# A3010_Adelaide_8MB_IDE.net
KiCad netlist of a schematic drawn in Altium Designer
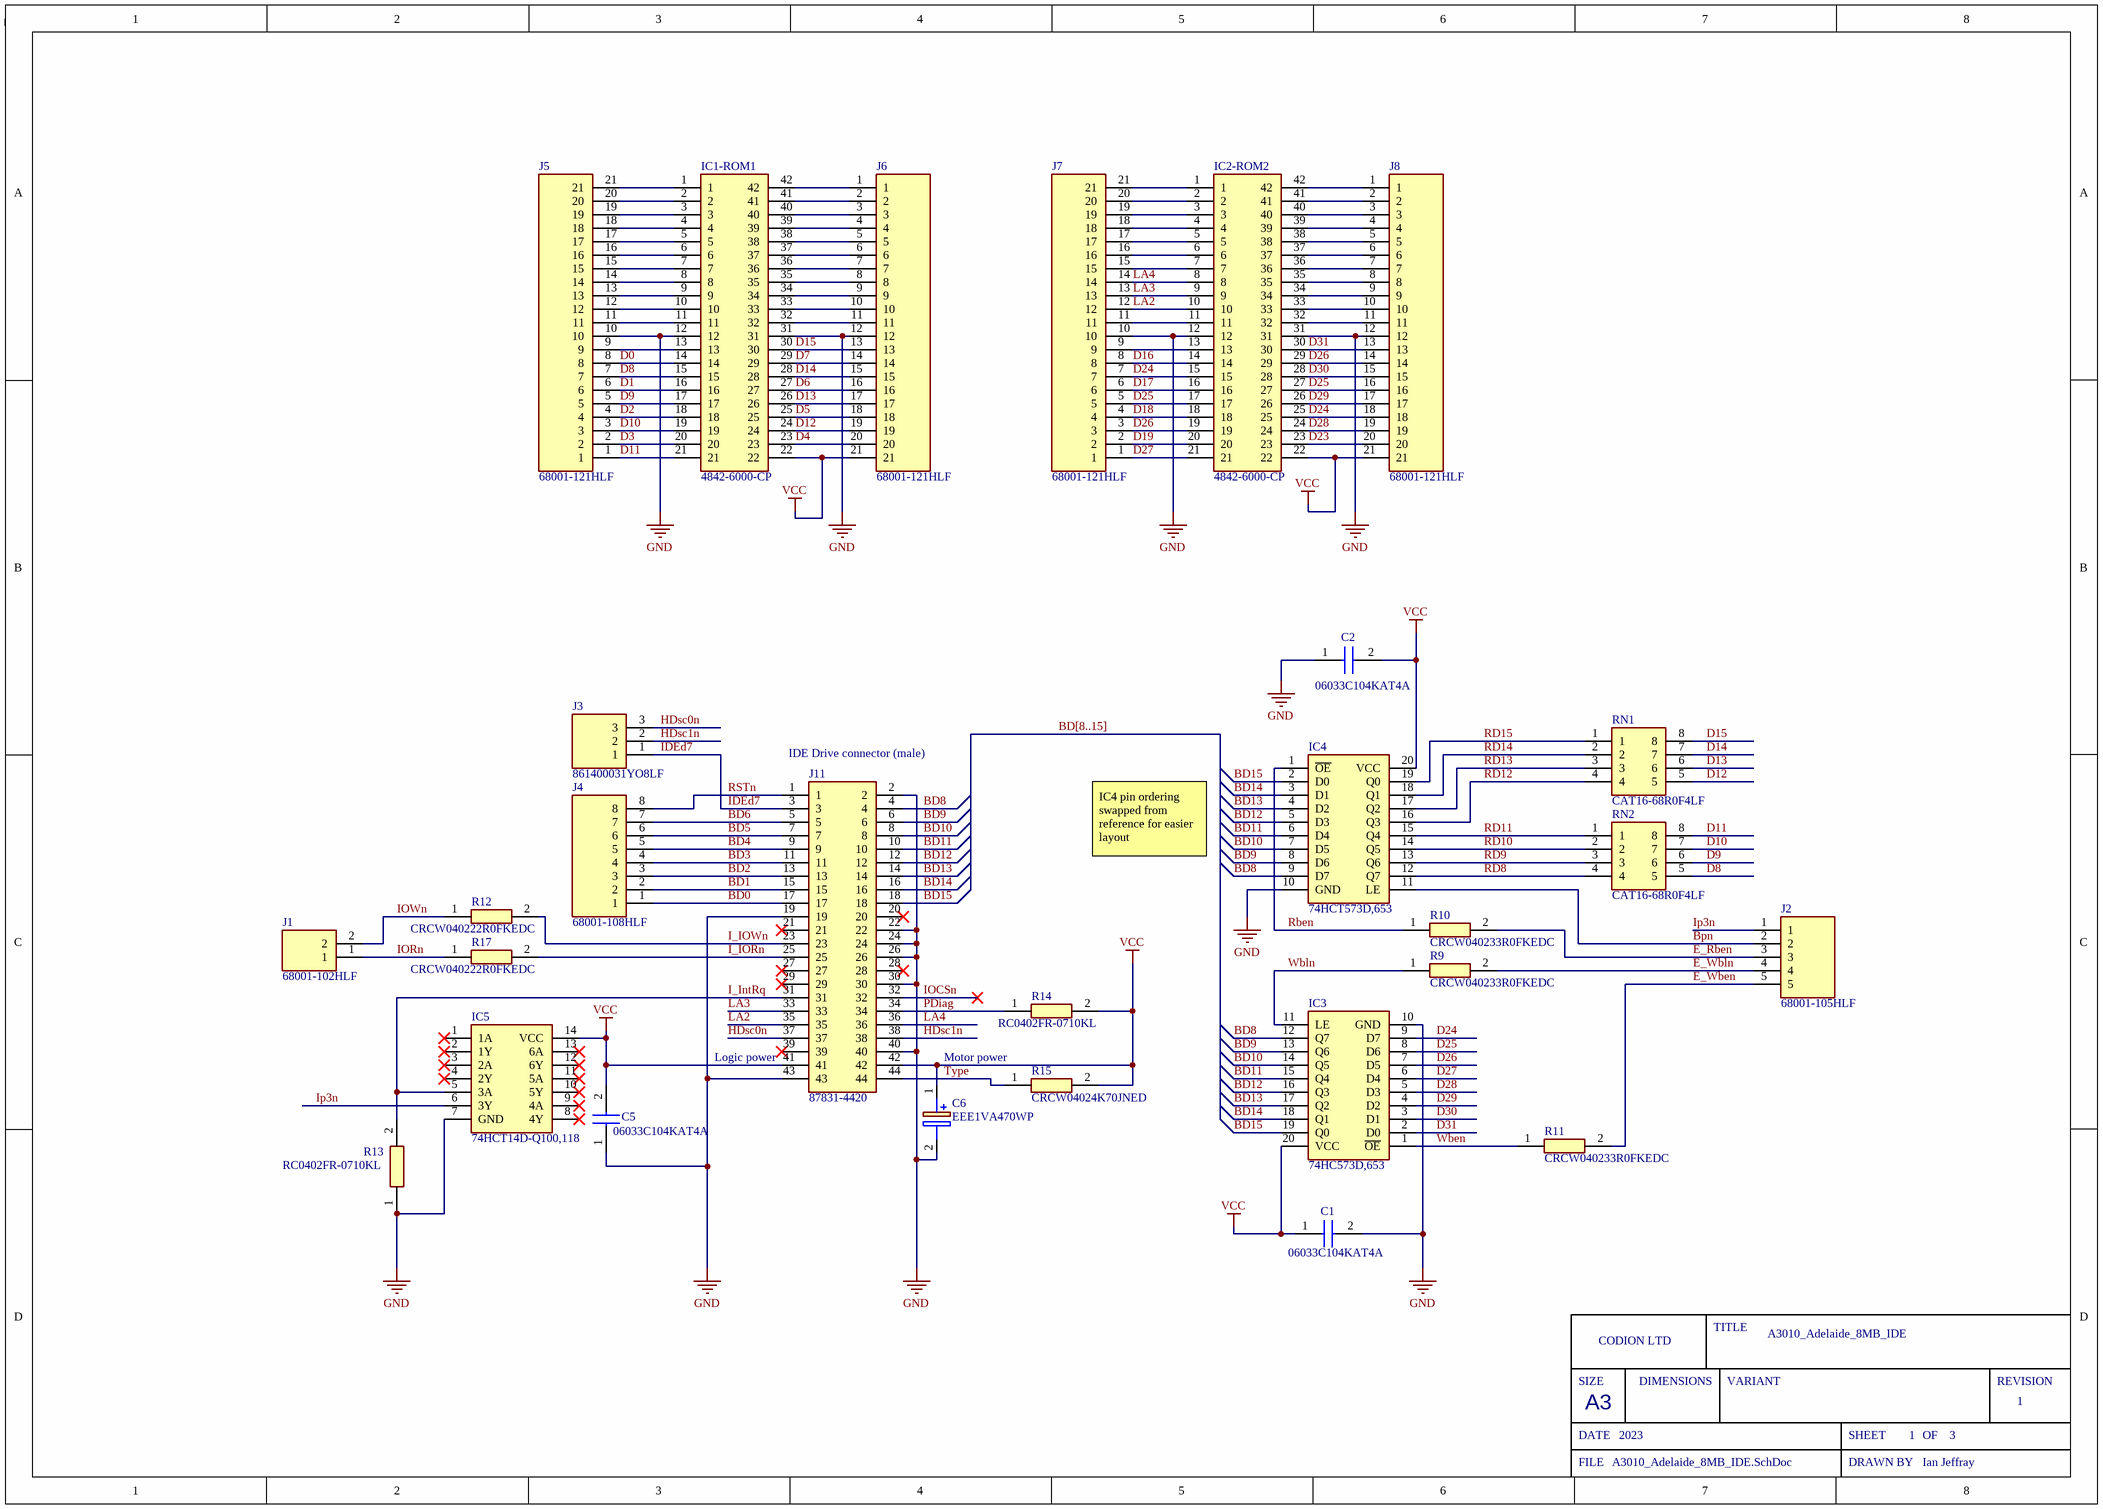
[diagram p0: A3010_Adelaide_8MB_IDE.SchDoc]

(export (version "E")
  (design (tool "Eeschema 10.0.6"))
  (components
    (comp (ref "C1")
      (value "06033C104KAT4A")
      (footprint "SamacSys:CAPC1608X90N")
      (description "Capacitor")
      (fields (field (name "MOUSER PART NUMBER") "581-06033C104KAT4A"))
      (libsource (lib "*") (part "06033C104KAT4A"))
    )
    (comp (ref "C2")
      (value "06033C104KAT4A")
      (footprint "SamacSys:CAPC1608X90N")
      (description "Capacitor")
      (fields (field (name "MOUSER PART NUMBER") "581-06033C104KAT4A"))
      (libsource (lib "*") (part "06033C104KAT4A"))
    )
    (comp (ref "C5")
      (value "06033C104KAT4A")
      (footprint "SamacSys:CAPC1608X90N")
      (description "Capacitor")
      (fields (field (name "MOUSER PART NUMBER") "581-06033C104KAT4A"))
      (libsource (lib "*") (part "06033C104KAT4A"))
    )
    (comp (ref "C6")
      (value "EEE1VA470WP")
      (footprint "SamacSys:EEE1AA101SP")
      (description "Capacitor Polarised")
      (libsource (lib "*") (part "EEE1VA470WP"))
    )
    (comp (ref "IC1-ROM1")
      (value "4842-6000-CP")
      (footprint "SamacSys:48426000CP")
      (description "Connector")
      (fields (field (name "MOUSER PART NUMBER") "517-4842-6000-CP"))
      (libsource (lib "*") (part "4842-6000-CP"))
    )
    (comp (ref "IC2-ROM2")
      (value "4842-6000-CP")
      (footprint "SamacSys:48426000CP")
      (description "Connector")
      (fields (field (name "MOUSER PART NUMBER") "517-4842-6000-CP"))
      (libsource (lib "*") (part "4842-6000-CP"))
    )
    (comp (ref "IC3")
      (value "74HC573D,653")
      (footprint "SamacSys:SOIC127P1032X265-20N")
      (description "Integrated Circuit")
      (fields (field (name "MOUSER PART NUMBER") "771-74HC573D-T"))
      (libsource (lib "*") (part "74HC573D,653"))
    )
    (comp (ref "IC4")
      (value "74HCT573D,653")
      (footprint "SamacSys:SOIC127P1032X265-20N")
      (description "Integrated Circuit")
      (fields (field (name "MOUSER PART NUMBER") "771-HCT573D653"))
      (libsource (lib "*") (part "74HCT573D,653"))
    )
    (comp (ref "IC5")
      (value "74HCT14D-Q100,118")
      (footprint "SamacSys:SOIC127P600X175-14N")
      (description "Integrated Circuit")
      (fields (field (name "MOUSER PART NUMBER") "771-74HCT14D-Q100118"))
      (libsource (lib "*") (part "74HCT14D-Q100,118"))
    )
    (comp (ref "J1")
      (value "68001-102HLF")
      (footprint "SamacSys:HDRV2W67P0X254_1X2_508X241X858P")
      (description "Connector")
      (fields (field (name "MOUSER PART NUMBER") "649-68001-102HLF"))
      (libsource (lib "*") (part "68001-102HLF"))
    )
    (comp (ref "J2")
      (value "68001-105HLF")
      (footprint "SamacSys:HDRV5W90P0X254_1X5_1270X241X1143P")
      (description "Connector")
      (fields (field (name "MOUSER PART NUMBER") "649-68001-105HLF"))
      (libsource (lib "*") (part "68001-105HLF"))
    )
    (comp (ref "J3")
      (value "861400031YO8LF")
      (footprint "SamacSys:HDRV3W63P0X254_1X3_762X254X980P")
      (description "Connector")
      (fields (field (name "MOUSER PART NUMBER") "649-861400031YO8LF"))
      (libsource (lib "*") (part "861400031YO8LF"))
    )
    (comp (ref "J4")
      (value "68001-108HLF")
      (footprint "SamacSys:HDRV8W90P0X254_1X8_2032X241X1143P")
      (description "Connector")
      (fields (field (name "MOUSER PART NUMBER") "649-68001-108HLF"))
      (libsource (lib "*") (part "68001-108HLF"))
    )
    (comp (ref "J5")
      (value "68001-121HLF")
      (footprint "SamacSys:HDRV21W67P0X254_1X21_5334X241X858P")
      (description "Connector")
      (fields (field (name "MOUSER PART NUMBER") "649-68001-121HLF"))
      (libsource (lib "") (part "68001-121HLF_1"))
    )
    (comp (ref "J6")
      (value "68001-121HLF")
      (footprint "SamacSys:HDRV21W67P0X254_1X21_5334X241X858P")
      (description "Connector")
      (fields (field (name "MOUSER PART NUMBER") "649-68001-121HLF"))
      (libsource (lib "*") (part "68001-121HLF"))
    )
    (comp (ref "J7")
      (value "68001-121HLF")
      (footprint "SamacSys:HDRV21W67P0X254_1X21_5334X241X858P")
      (description "Connector")
      (fields (field (name "MOUSER PART NUMBER") "649-68001-121HLF"))
      (libsource (lib "") (part "68001-121HLF_1"))
    )
    (comp (ref "J8")
      (value "68001-121HLF")
      (footprint "SamacSys:HDRV21W67P0X254_1X21_5334X241X858P")
      (description "Connector")
      (fields (field (name "MOUSER PART NUMBER") "649-68001-121HLF"))
      (libsource (lib "*") (part "68001-121HLF"))
    )
    (comp (ref "J11")
      (value "87831-4420")
      (footprint "SamacSys:SHDR44W55P200_2X22_4665X630X640P")
      (description "Connector")
      (fields (field (name "MOUSER PART NUMBER") "538-87831-4420"))
      (libsource (lib "*") (part "87831-4420"))
    )
    (comp (ref "R9")
      (value "CRCW040233R0FKEDC")
      (footprint "SamacSys:RESC1005X35N")
      (description "Resistor")
      (fields (field (name "MOUSER PART NUMBER") "71-CRCW040233R0FKEDC"))
      (libsource (lib "*") (part "CRCW040233R0FKEDC"))
    )
    (comp (ref "R10")
      (value "CRCW040233R0FKEDC")
      (footprint "SamacSys:RESC1005X35N")
      (description "Resistor")
      (fields (field (name "MOUSER PART NUMBER") "71-CRCW040233R0FKEDC"))
      (libsource (lib "*") (part "CRCW040233R0FKEDC"))
    )
    (comp (ref "R11")
      (value "CRCW040233R0FKEDC")
      (footprint "SamacSys:RESC1005X35N")
      (description "Resistor")
      (fields (field (name "MOUSER PART NUMBER") "71-CRCW040233R0FKEDC"))
      (libsource (lib "*") (part "CRCW040233R0FKEDC"))
    )
    (comp (ref "R12")
      (value "CRCW040222R0FKEDC")
      (footprint "SamacSys:RESC1005X35N")
      (description "Resistor")
      (fields (field (name "MOUSER PART NUMBER") "71-CRCW040222R0FKEDC"))
      (libsource (lib "*") (part "CRCW040222R0FKEDC"))
    )
    (comp (ref "R13")
      (value "RC0402FR-0710KL")
      (footprint "SamacSys:RESC1005X40N")
      (description "Resistor")
      (fields (field (name "MOUSER PART NUMBER") "603-RC0402FR-0710KL"))
      (libsource (lib "*") (part "RC0402FR-0710KL"))
    )
    (comp (ref "R14")
      (value "RC0402FR-0710KL")
      (footprint "SamacSys:RESC1005X40N")
      (description "Resistor")
      (fields (field (name "MOUSER PART NUMBER") "603-RC0402FR-0710KL"))
      (libsource (lib "") (part "RC0402FR-0710KL_1"))
    )
    (comp (ref "R15")
      (value "CRCW04024K70JNED")
      (footprint "SamacSys:RESC1005X40N")
      (description "Resistor")
      (fields (field (name "MOUSER PART NUMBER") "71-CRCW0402J-4.7K-E3"))
      (libsource (lib "*") (part "CRCW04024K70JNED"))
    )
    (comp (ref "R17")
      (value "CRCW040222R0FKEDC")
      (footprint "SamacSys:RESC1005X35N")
      (description "Resistor")
      (fields (field (name "MOUSER PART NUMBER") "71-CRCW040222R0FKEDC"))
      (libsource (lib "*") (part "CRCW040222R0FKEDC"))
    )
    (comp (ref "RN1")
      (value "CAT16-68R0F4LF")
      (footprint "SamacSys:CAT1668R0F4LF")
      (description "Resistor Network")
      (fields (field (name "MOUSER PART NUMBER") "652-CAT16-68R0F4LF"))
      (libsource (lib "*") (part "CAT16-68R0F4LF"))
    )
    (comp (ref "RN2")
      (value "CAT16-68R0F4LF")
      (footprint "SamacSys:CAT1668R0F4LF")
      (description "Resistor Network")
      (fields (field (name "MOUSER PART NUMBER") "652-CAT16-68R0F4LF"))
      (libsource (lib "*") (part "CAT16-68R0F4LF"))
    )
  )
  (nets
    (net (code "1") (name "/BD0") (class "Default")
      (node (ref "J11") (pin "17") (pinfunction "17_17") (pintype "passive"))
      (node (ref "J4") (pin "1") (pinfunction "1_1") (pintype "passive"))
    )
    (net (code "2") (name "/BD1") (class "Default")
      (node (ref "J11") (pin "15") (pinfunction "15_15") (pintype "passive"))
      (node (ref "J4") (pin "2") (pinfunction "2_2") (pintype "passive"))
    )
    (net (code "3") (name "/BD2") (class "Default")
      (node (ref "J11") (pin "13") (pinfunction "13_13") (pintype "passive"))
      (node (ref "J4") (pin "3") (pinfunction "3_3") (pintype "passive"))
    )
    (net (code "4") (name "/BD3") (class "Default")
      (node (ref "J11") (pin "11") (pinfunction "11_11") (pintype "passive"))
      (node (ref "J4") (pin "4") (pinfunction "4_4") (pintype "passive"))
    )
    (net (code "5") (name "/BD4") (class "Default")
      (node (ref "J11") (pin "9") (pinfunction "9_9") (pintype "passive"))
      (node (ref "J4") (pin "5") (pinfunction "5_5") (pintype "passive"))
    )
    (net (code "6") (name "/BD5") (class "Default")
      (node (ref "J11") (pin "7") (pinfunction "7_7") (pintype "passive"))
      (node (ref "J4") (pin "6") (pinfunction "6_6") (pintype "passive"))
    )
    (net (code "7") (name "/BD6") (class "Default")
      (node (ref "J11") (pin "5") (pinfunction "5_5") (pintype "passive"))
      (node (ref "J4") (pin "7") (pinfunction "7_7") (pintype "passive"))
    )
    (net (code "8") (name "/BD8") (class "Default")
      (node (ref "IC3") (pin "12") (pinfunction "Q7_12") (pintype "passive"))
      (node (ref "IC4") (pin "9") (pinfunction "D7_9") (pintype "passive"))
      (node (ref "J11") (pin "4") (pinfunction "4_4") (pintype "passive"))
    )
    (net (code "9") (name "/BD9") (class "Default")
      (node (ref "IC3") (pin "13") (pinfunction "Q6_13") (pintype "passive"))
      (node (ref "IC4") (pin "8") (pinfunction "D6_8") (pintype "passive"))
      (node (ref "J11") (pin "6") (pinfunction "6_6") (pintype "passive"))
    )
    (net (code "10") (name "/BD10") (class "Default")
      (node (ref "IC3") (pin "14") (pinfunction "Q5_14") (pintype "passive"))
      (node (ref "IC4") (pin "7") (pinfunction "D5_7") (pintype "passive"))
      (node (ref "J11") (pin "8") (pinfunction "8_8") (pintype "passive"))
    )
    (net (code "11") (name "/BD11") (class "Default")
      (node (ref "IC3") (pin "15") (pinfunction "Q4_15") (pintype "passive"))
      (node (ref "IC4") (pin "6") (pinfunction "D4_6") (pintype "passive"))
      (node (ref "J11") (pin "10") (pinfunction "10_10") (pintype "passive"))
    )
    (net (code "12") (name "/BD12") (class "Default")
      (node (ref "IC3") (pin "16") (pinfunction "Q3_16") (pintype "passive"))
      (node (ref "IC4") (pin "5") (pinfunction "D3_5") (pintype "passive"))
      (node (ref "J11") (pin "12") (pinfunction "12_12") (pintype "passive"))
    )
    (net (code "13") (name "/BD13") (class "Default")
      (node (ref "IC3") (pin "17") (pinfunction "Q2_17") (pintype "passive"))
      (node (ref "IC4") (pin "4") (pinfunction "D2_4") (pintype "passive"))
      (node (ref "J11") (pin "14") (pinfunction "14_14") (pintype "passive"))
    )
    (net (code "14") (name "/BD14") (class "Default")
      (node (ref "IC3") (pin "18") (pinfunction "Q1_18") (pintype "passive"))
      (node (ref "IC4") (pin "3") (pinfunction "D1_3") (pintype "passive"))
      (node (ref "J11") (pin "16") (pinfunction "16_16") (pintype "passive"))
    )
    (net (code "15") (name "/BD15") (class "Default")
      (node (ref "IC3") (pin "19") (pinfunction "Q0_19") (pintype "passive"))
      (node (ref "IC4") (pin "2") (pinfunction "D0_2") (pintype "passive"))
      (node (ref "J11") (pin "18") (pinfunction "18_18") (pintype "passive"))
    )
    (net (code "17") (name "/Bpn") (class "Default")
      (node (ref "IC4") (pin "11") (pinfunction "LE_11") (pintype "passive"))
      (node (ref "J2") (pin "2") (pinfunction "2_2") (pintype "passive"))
    )
    (net (code "18") (name "/D0") (class "Default")
      (node (ref "IC1-ROM1") (pin "14") (pinfunction "14_14") (pintype "passive"))
      (node (ref "J5") (pin "8") (pinfunction "8_8") (pintype "passive"))
    )
    (net (code "19") (name "/D1") (class "Default")
      (node (ref "IC1-ROM1") (pin "16") (pinfunction "16_16") (pintype "passive"))
      (node (ref "J5") (pin "6") (pinfunction "6_6") (pintype "passive"))
    )
    (net (code "20") (name "/D2") (class "Default")
      (node (ref "IC1-ROM1") (pin "18") (pinfunction "18_18") (pintype "passive"))
      (node (ref "J5") (pin "4") (pinfunction "4_4") (pintype "passive"))
    )
    (net (code "21") (name "/D3") (class "Default")
      (node (ref "IC1-ROM1") (pin "20") (pinfunction "20_20") (pintype "passive"))
      (node (ref "J5") (pin "2") (pinfunction "2_2") (pintype "passive"))
    )
    (net (code "22") (name "/D4") (class "Default")
      (node (ref "IC1-ROM1") (pin "23") (pinfunction "23_23") (pintype "passive"))
      (node (ref "J6") (pin "20") (pinfunction "20_20") (pintype "passive"))
    )
    (net (code "23") (name "/D5") (class "Default")
      (node (ref "IC1-ROM1") (pin "25") (pinfunction "25_25") (pintype "passive"))
      (node (ref "J6") (pin "18") (pinfunction "18_18") (pintype "passive"))
    )
    (net (code "24") (name "/D6") (class "Default")
      (node (ref "IC1-ROM1") (pin "27") (pinfunction "27_27") (pintype "passive"))
      (node (ref "J6") (pin "16") (pinfunction "16_16") (pintype "passive"))
    )
    (net (code "25") (name "/D7") (class "Default")
      (node (ref "IC1-ROM1") (pin "29") (pinfunction "29_29") (pintype "passive"))
      (node (ref "J6") (pin "14") (pinfunction "14_14") (pintype "passive"))
    )
    (net (code "26") (name "/D8") (class "Default")
      (node (ref "IC1-ROM1") (pin "15") (pinfunction "15_15") (pintype "passive"))
      (node (ref "J5") (pin "7") (pinfunction "7_7") (pintype "passive"))
      (node (ref "RN2") (pin "5") (pinfunction "5_5") (pintype "passive"))
    )
    (net (code "27") (name "/D9") (class "Default")
      (node (ref "IC1-ROM1") (pin "17") (pinfunction "17_17") (pintype "passive"))
      (node (ref "J5") (pin "5") (pinfunction "5_5") (pintype "passive"))
      (node (ref "RN2") (pin "6") (pinfunction "6_6") (pintype "passive"))
    )
    (net (code "28") (name "/D10") (class "Default")
      (node (ref "IC1-ROM1") (pin "19") (pinfunction "19_19") (pintype "passive"))
      (node (ref "J5") (pin "3") (pinfunction "3_3") (pintype "passive"))
      (node (ref "RN2") (pin "7") (pinfunction "7_7") (pintype "passive"))
    )
    (net (code "29") (name "/D11") (class "Default")
      (node (ref "IC1-ROM1") (pin "21") (pinfunction "21_21") (pintype "passive"))
      (node (ref "J5") (pin "1") (pinfunction "1_1") (pintype "passive"))
      (node (ref "RN2") (pin "8") (pinfunction "8_8") (pintype "passive"))
    )
    (net (code "30") (name "/D12") (class "Default")
      (node (ref "IC1-ROM1") (pin "24") (pinfunction "24_24") (pintype "passive"))
      (node (ref "J6") (pin "19") (pinfunction "19_19") (pintype "passive"))
      (node (ref "RN1") (pin "5") (pinfunction "5_5") (pintype "passive"))
    )
    (net (code "31") (name "/D13") (class "Default")
      (node (ref "IC1-ROM1") (pin "26") (pinfunction "26_26") (pintype "passive"))
      (node (ref "J6") (pin "17") (pinfunction "17_17") (pintype "passive"))
      (node (ref "RN1") (pin "6") (pinfunction "6_6") (pintype "passive"))
    )
    (net (code "32") (name "/D14") (class "Default")
      (node (ref "IC1-ROM1") (pin "28") (pinfunction "28_28") (pintype "passive"))
      (node (ref "J6") (pin "15") (pinfunction "15_15") (pintype "passive"))
      (node (ref "RN1") (pin "7") (pinfunction "7_7") (pintype "passive"))
    )
    (net (code "33") (name "/D15") (class "Default")
      (node (ref "IC1-ROM1") (pin "30") (pinfunction "30_30") (pintype "passive"))
      (node (ref "J6") (pin "13") (pinfunction "13_13") (pintype "passive"))
      (node (ref "RN1") (pin "8") (pinfunction "8_8") (pintype "passive"))
    )
    (net (code "34") (name "/D16") (class "Default")
      (node (ref "IC2-ROM2") (pin "14") (pinfunction "14_14") (pintype "passive"))
      (node (ref "J7") (pin "8") (pinfunction "8_8") (pintype "passive"))
    )
    (net (code "35") (name "/D17") (class "Default")
      (node (ref "IC2-ROM2") (pin "16") (pinfunction "16_16") (pintype "passive"))
      (node (ref "J7") (pin "6") (pinfunction "6_6") (pintype "passive"))
    )
    (net (code "36") (name "/D18") (class "Default")
      (node (ref "IC2-ROM2") (pin "18") (pinfunction "18_18") (pintype "passive"))
      (node (ref "J7") (pin "4") (pinfunction "4_4") (pintype "passive"))
    )
    (net (code "37") (name "/D19") (class "Default")
      (node (ref "IC2-ROM2") (pin "20") (pinfunction "20_20") (pintype "passive"))
      (node (ref "J7") (pin "2") (pinfunction "2_2") (pintype "passive"))
    )
    (net (code "38") (name "/D23") (class "Default")
      (node (ref "IC2-ROM2") (pin "23") (pinfunction "23_23") (pintype "passive"))
      (node (ref "J8") (pin "20") (pinfunction "20_20") (pintype "passive"))
    )
    (net (code "39") (name "/D24") (class "Default")
      (node (ref "IC2-ROM2") (pin "15") (pinfunction "15_15") (pintype "passive"))
      (node (ref "IC2-ROM2") (pin "25") (pinfunction "25_25") (pintype "passive"))
      (node (ref "IC3") (pin "9") (pinfunction "D7_9") (pintype "passive"))
      (node (ref "J7") (pin "7") (pinfunction "7_7") (pintype "passive"))
      (node (ref "J8") (pin "18") (pinfunction "18_18") (pintype "passive"))
    )
    (net (code "40") (name "/D25") (class "Default")
      (node (ref "IC2-ROM2") (pin "17") (pinfunction "17_17") (pintype "passive"))
      (node (ref "IC2-ROM2") (pin "27") (pinfunction "27_27") (pintype "passive"))
      (node (ref "IC3") (pin "8") (pinfunction "D6_8") (pintype "passive"))
      (node (ref "J7") (pin "5") (pinfunction "5_5") (pintype "passive"))
      (node (ref "J8") (pin "16") (pinfunction "16_16") (pintype "passive"))
    )
    (net (code "41") (name "/D26") (class "Default")
      (node (ref "IC2-ROM2") (pin "19") (pinfunction "19_19") (pintype "passive"))
      (node (ref "IC2-ROM2") (pin "29") (pinfunction "29_29") (pintype "passive"))
      (node (ref "IC3") (pin "7") (pinfunction "D5_7") (pintype "passive"))
      (node (ref "J7") (pin "3") (pinfunction "3_3") (pintype "passive"))
      (node (ref "J8") (pin "14") (pinfunction "14_14") (pintype "passive"))
    )
    (net (code "42") (name "/D27") (class "Default")
      (node (ref "IC2-ROM2") (pin "21") (pinfunction "21_21") (pintype "passive"))
      (node (ref "IC3") (pin "6") (pinfunction "D4_6") (pintype "passive"))
      (node (ref "J7") (pin "1") (pinfunction "1_1") (pintype "passive"))
    )
    (net (code "43") (name "/D28") (class "Default")
      (node (ref "IC2-ROM2") (pin "24") (pinfunction "24_24") (pintype "passive"))
      (node (ref "IC3") (pin "5") (pinfunction "D3_5") (pintype "passive"))
      (node (ref "J8") (pin "19") (pinfunction "19_19") (pintype "passive"))
    )
    (net (code "44") (name "/D29") (class "Default")
      (node (ref "IC2-ROM2") (pin "26") (pinfunction "26_26") (pintype "passive"))
      (node (ref "IC3") (pin "4") (pinfunction "D2_4") (pintype "passive"))
      (node (ref "J8") (pin "17") (pinfunction "17_17") (pintype "passive"))
    )
    (net (code "45") (name "/D30") (class "Default")
      (node (ref "IC2-ROM2") (pin "28") (pinfunction "28_28") (pintype "passive"))
      (node (ref "IC3") (pin "3") (pinfunction "D1_3") (pintype "passive"))
      (node (ref "J8") (pin "15") (pinfunction "15_15") (pintype "passive"))
    )
    (net (code "46") (name "/D31") (class "Default")
      (node (ref "IC2-ROM2") (pin "30") (pinfunction "30_30") (pintype "passive"))
      (node (ref "IC3") (pin "2") (pinfunction "D0_2") (pintype "passive"))
      (node (ref "J8") (pin "13") (pinfunction "13_13") (pintype "passive"))
    )
    (net (code "47") (name "/E_Rben") (class "Default")
      (node (ref "J2") (pin "3") (pinfunction "3_3") (pintype "passive"))
      (node (ref "R10") (pin "2") (pinfunction "2_2") (pintype "passive"))
    )
    (net (code "48") (name "/E_Wben") (class "Default")
      (node (ref "J2") (pin "5") (pinfunction "5_5") (pintype "passive"))
      (node (ref "R11") (pin "2") (pinfunction "2_2") (pintype "passive"))
    )
    (net (code "49") (name "/E_Wbln") (class "Default")
      (node (ref "J2") (pin "4") (pinfunction "4_4") (pintype "passive"))
      (node (ref "R9") (pin "2") (pinfunction "2_2") (pintype "passive"))
    )
    (net (code "50") (name "/HDsc0n") (class "Default")
      (node (ref "J11") (pin "37") (pinfunction "37_37") (pintype "passive"))
      (node (ref "J3") (pin "3") (pinfunction "3_3") (pintype "passive"))
    )
    (net (code "51") (name "/HDsc1n") (class "Default")
      (node (ref "J11") (pin "38") (pinfunction "38_38") (pintype "passive"))
      (node (ref "J3") (pin "2") (pinfunction "2_2") (pintype "passive"))
    )
    (net (code "52") (name "/IDEd7") (class "Default")
      (node (ref "J11") (pin "3") (pinfunction "3_3") (pintype "passive"))
      (node (ref "J3") (pin "1") (pinfunction "1_1") (pintype "passive"))
    )
    (net (code "53") (name "/IOCSn") (class "Default")
      (node (ref "J11") (pin "32") (pinfunction "32_32") (pintype "passive+no_connect"))
    )
    (net (code "54") (name "/IORn") (class "Default")
      (node (ref "J1") (pin "1") (pinfunction "1_1") (pintype "passive"))
      (node (ref "R17") (pin "1") (pinfunction "1_1") (pintype "passive"))
    )
    (net (code "55") (name "/IOWn") (class "Default")
      (node (ref "J1") (pin "2") (pinfunction "2_2") (pintype "passive"))
      (node (ref "R12") (pin "1") (pinfunction "1_1") (pintype "passive"))
    )
    (net (code "56") (name "/I_IORn") (class "Default")
      (node (ref "J11") (pin "25") (pinfunction "25_25") (pintype "passive"))
      (node (ref "R17") (pin "2") (pinfunction "2_2") (pintype "passive"))
    )
    (net (code "57") (name "/I_IOWn") (class "Default")
      (node (ref "J11") (pin "23") (pinfunction "23_23") (pintype "passive"))
      (node (ref "R12") (pin "2") (pinfunction "2_2") (pintype "passive"))
    )
    (net (code "58") (name "/I_IntRq") (class "Default")
      (node (ref "IC5") (pin "5") (pinfunction "3A_5") (pintype "passive"))
      (node (ref "J11") (pin "31") (pinfunction "31_31") (pintype "passive"))
      (node (ref "R13") (pin "2") (pinfunction "2_2") (pintype "passive"))
    )
    (net (code "59") (name "/Ip3n") (class "Default")
      (node (ref "IC5") (pin "6") (pinfunction "3Y_6") (pintype "passive"))
      (node (ref "J2") (pin "1") (pinfunction "1_1") (pintype "passive"))
    )
    (net (code "60") (name "/LA2") (class "Default")
      (node (ref "IC2-ROM2") (pin "10") (pinfunction "10_10") (pintype "passive"))
      (node (ref "J11") (pin "35") (pinfunction "35_35") (pintype "passive"))
      (node (ref "J7") (pin "12") (pinfunction "12_12") (pintype "passive"))
    )
    (net (code "61") (name "/LA3") (class "Default")
      (node (ref "IC2-ROM2") (pin "9") (pinfunction "9_9") (pintype "passive"))
      (node (ref "J11") (pin "33") (pinfunction "33_33") (pintype "passive"))
      (node (ref "J7") (pin "13") (pinfunction "13_13") (pintype "passive"))
    )
    (net (code "62") (name "/LA4") (class "Default")
      (node (ref "IC2-ROM2") (pin "8") (pinfunction "8_8") (pintype "passive"))
      (node (ref "J11") (pin "36") (pinfunction "36_36") (pintype "passive"))
      (node (ref "J7") (pin "14") (pinfunction "14_14") (pintype "passive"))
    )
    (net (code "63") (name "/PDiag") (class "Default")
      (node (ref "J11") (pin "34") (pinfunction "34_34") (pintype "passive"))
      (node (ref "R14") (pin "1") (pinfunction "1_1") (pintype "passive"))
    )
    (net (code "64") (name "/RD8") (class "Default")
      (node (ref "IC4") (pin "12") (pinfunction "Q7_12") (pintype "passive"))
      (node (ref "RN2") (pin "4") (pinfunction "4_4") (pintype "passive"))
    )
    (net (code "65") (name "/RD9") (class "Default")
      (node (ref "IC4") (pin "13") (pinfunction "Q6_13") (pintype "passive"))
      (node (ref "RN2") (pin "3") (pinfunction "3_3") (pintype "passive"))
    )
    (net (code "66") (name "/RD10") (class "Default")
      (node (ref "IC4") (pin "14") (pinfunction "Q5_14") (pintype "passive"))
      (node (ref "RN2") (pin "2") (pinfunction "2_2") (pintype "passive"))
    )
    (net (code "67") (name "/RD11") (class "Default")
      (node (ref "IC4") (pin "15") (pinfunction "Q4_15") (pintype "passive"))
      (node (ref "RN2") (pin "1") (pinfunction "1_1") (pintype "passive"))
    )
    (net (code "68") (name "/RD12") (class "Default")
      (node (ref "IC4") (pin "16") (pinfunction "Q3_16") (pintype "passive"))
      (node (ref "RN1") (pin "4") (pinfunction "4_4") (pintype "passive"))
    )
    (net (code "69") (name "/RD13") (class "Default")
      (node (ref "IC4") (pin "17") (pinfunction "Q2_17") (pintype "passive"))
      (node (ref "RN1") (pin "3") (pinfunction "3_3") (pintype "passive"))
    )
    (net (code "70") (name "/RD14") (class "Default")
      (node (ref "IC4") (pin "18") (pinfunction "Q1_18") (pintype "passive"))
      (node (ref "RN1") (pin "2") (pinfunction "2_2") (pintype "passive"))
    )
    (net (code "71") (name "/RD15") (class "Default")
      (node (ref "IC4") (pin "19") (pinfunction "Q0_19") (pintype "passive"))
      (node (ref "RN1") (pin "1") (pinfunction "1_1") (pintype "passive"))
    )
    (net (code "72") (name "/RSTn") (class "Default")
      (node (ref "J11") (pin "1") (pinfunction "1_1") (pintype "passive"))
      (node (ref "J4") (pin "8") (pinfunction "8_8") (pintype "passive"))
    )
    (net (code "73") (name "/Rben") (class "Default")
      (node (ref "IC4") (pin "1") (pinfunction "~{OE}_1") (pintype "passive"))
      (node (ref "R10") (pin "1") (pinfunction "1_1") (pintype "passive"))
    )
    (net (code "74") (name "/Type") (class "Default")
      (node (ref "J11") (pin "44") (pinfunction "44_44") (pintype "passive"))
      (node (ref "R15") (pin "1") (pinfunction "1_1") (pintype "passive"))
    )
    (net (code "75") (name "/Wben") (class "Default")
      (node (ref "IC3") (pin "1") (pinfunction "~{OE}_1") (pintype "passive"))
      (node (ref "R11") (pin "1") (pinfunction "1_1") (pintype "passive"))
    )
    (net (code "76") (name "/Wbln") (class "Default")
      (node (ref "IC3") (pin "11") (pinfunction "LE_11") (pintype "passive"))
      (node (ref "R9") (pin "1") (pinfunction "1_1") (pintype "passive"))
    )
    (net (code "77") (name "GND") (class "Default")
      (node (ref "C1") (pin "2") (pinfunction "2_2") (pintype "passive"))
      (node (ref "C2") (pin "1") (pinfunction "1_1") (pintype "passive"))
      (node (ref "C5") (pin "1") (pinfunction "1_1") (pintype "passive"))
      (node (ref "C6") (pin "2") (pinfunction "-_2") (pintype "passive"))
      (node (ref "IC1-ROM1") (pin "12") (pinfunction "12_12") (pintype "passive"))
      (node (ref "IC1-ROM1") (pin "31") (pinfunction "31_31") (pintype "passive"))
      (node (ref "IC2-ROM2") (pin "12") (pinfunction "12_12") (pintype "passive"))
      (node (ref "IC2-ROM2") (pin "31") (pinfunction "31_31") (pintype "passive"))
      (node (ref "IC3") (pin "10") (pinfunction "GND_10") (pintype "passive"))
      (node (ref "IC4") (pin "10") (pinfunction "GND_10") (pintype "passive"))
      (node (ref "IC5") (pin "7") (pinfunction "GND_7") (pintype "passive"))
      (node (ref "J11") (pin "19") (pinfunction "19_19") (pintype "passive"))
      (node (ref "J11") (pin "2") (pinfunction "2_2") (pintype "passive"))
      (node (ref "J11") (pin "22") (pinfunction "22_22") (pintype "passive"))
      (node (ref "J11") (pin "24") (pinfunction "24_24") (pintype "passive"))
      (node (ref "J11") (pin "26") (pinfunction "26_26") (pintype "passive"))
      (node (ref "J11") (pin "30") (pinfunction "30_30") (pintype "passive"))
      (node (ref "J11") (pin "40") (pinfunction "40_40") (pintype "passive"))
      (node (ref "J11") (pin "43") (pinfunction "43_43") (pintype "passive"))
      (node (ref "J5") (pin "10") (pinfunction "10_10") (pintype "passive"))
      (node (ref "J6") (pin "12") (pinfunction "12_12") (pintype "passive"))
      (node (ref "J7") (pin "10") (pinfunction "10_10") (pintype "passive"))
      (node (ref "J8") (pin "12") (pinfunction "12_12") (pintype "passive"))
      (node (ref "R13") (pin "1") (pinfunction "1_1") (pintype "passive"))
    )
    (net (code "78") (name "Net-(IC1-ROM1-Pad1)") (class "Default")
      (node (ref "IC1-ROM1") (pin "1") (pinfunction "1_1") (pintype "passive"))
      (node (ref "J5") (pin "21") (pinfunction "21_21") (pintype "passive"))
    )
    (net (code "79") (name "Net-(IC1-ROM1-Pad2)") (class "Default")
      (node (ref "IC1-ROM1") (pin "2") (pinfunction "2_2") (pintype "passive"))
      (node (ref "J5") (pin "20") (pinfunction "20_20") (pintype "passive"))
    )
    (net (code "80") (name "Net-(IC1-ROM1-Pad3)") (class "Default")
      (node (ref "IC1-ROM1") (pin "3") (pinfunction "3_3") (pintype "passive"))
      (node (ref "J5") (pin "19") (pinfunction "19_19") (pintype "passive"))
    )
    (net (code "81") (name "Net-(IC1-ROM1-Pad4)") (class "Default")
      (node (ref "IC1-ROM1") (pin "4") (pinfunction "4_4") (pintype "passive"))
      (node (ref "J5") (pin "18") (pinfunction "18_18") (pintype "passive"))
    )
    (net (code "82") (name "Net-(IC1-ROM1-Pad5)") (class "Default")
      (node (ref "IC1-ROM1") (pin "5") (pinfunction "5_5") (pintype "passive"))
      (node (ref "J5") (pin "17") (pinfunction "17_17") (pintype "passive"))
    )
    (net (code "83") (name "Net-(IC1-ROM1-Pad6)") (class "Default")
      (node (ref "IC1-ROM1") (pin "6") (pinfunction "6_6") (pintype "passive"))
      (node (ref "J5") (pin "16") (pinfunction "16_16") (pintype "passive"))
    )
    (net (code "84") (name "Net-(IC1-ROM1-Pad7)") (class "Default")
      (node (ref "IC1-ROM1") (pin "7") (pinfunction "7_7") (pintype "passive"))
      (node (ref "J5") (pin "15") (pinfunction "15_15") (pintype "passive"))
    )
    (net (code "85") (name "Net-(IC1-ROM1-Pad8)") (class "Default")
      (node (ref "IC1-ROM1") (pin "8") (pinfunction "8_8") (pintype "passive"))
      (node (ref "J5") (pin "14") (pinfunction "14_14") (pintype "passive"))
    )
    (net (code "86") (name "Net-(IC1-ROM1-Pad9)") (class "Default")
      (node (ref "IC1-ROM1") (pin "9") (pinfunction "9_9") (pintype "passive"))
      (node (ref "J5") (pin "13") (pinfunction "13_13") (pintype "passive"))
    )
    (net (code "87") (name "Net-(IC1-ROM1-Pad10)") (class "Default")
      (node (ref "IC1-ROM1") (pin "10") (pinfunction "10_10") (pintype "passive"))
      (node (ref "J5") (pin "12") (pinfunction "12_12") (pintype "passive"))
    )
    (net (code "88") (name "Net-(IC1-ROM1-Pad11)") (class "Default")
      (node (ref "IC1-ROM1") (pin "11") (pinfunction "11_11") (pintype "passive"))
      (node (ref "J5") (pin "11") (pinfunction "11_11") (pintype "passive"))
    )
    (net (code "89") (name "Net-(IC1-ROM1-Pad13)") (class "Default")
      (node (ref "IC1-ROM1") (pin "13") (pinfunction "13_13") (pintype "passive"))
      (node (ref "J5") (pin "9") (pinfunction "9_9") (pintype "passive"))
    )
    (net (code "90") (name "Net-(IC1-ROM1-Pad32)") (class "Default")
      (node (ref "IC1-ROM1") (pin "32") (pinfunction "32_32") (pintype "passive"))
      (node (ref "J6") (pin "11") (pinfunction "11_11") (pintype "passive"))
    )
    (net (code "91") (name "Net-(IC1-ROM1-Pad33)") (class "Default")
      (node (ref "IC1-ROM1") (pin "33") (pinfunction "33_33") (pintype "passive"))
      (node (ref "J6") (pin "10") (pinfunction "10_10") (pintype "passive"))
    )
    (net (code "92") (name "Net-(IC1-ROM1-Pad34)") (class "Default")
      (node (ref "IC1-ROM1") (pin "34") (pinfunction "34_34") (pintype "passive"))
      (node (ref "J6") (pin "9") (pinfunction "9_9") (pintype "passive"))
    )
    (net (code "93") (name "Net-(IC1-ROM1-Pad35)") (class "Default")
      (node (ref "IC1-ROM1") (pin "35") (pinfunction "35_35") (pintype "passive"))
      (node (ref "J6") (pin "8") (pinfunction "8_8") (pintype "passive"))
    )
    (net (code "94") (name "Net-(IC1-ROM1-Pad36)") (class "Default")
      (node (ref "IC1-ROM1") (pin "36") (pinfunction "36_36") (pintype "passive"))
      (node (ref "J6") (pin "7") (pinfunction "7_7") (pintype "passive"))
    )
    (net (code "95") (name "Net-(IC1-ROM1-Pad37)") (class "Default")
      (node (ref "IC1-ROM1") (pin "37") (pinfunction "37_37") (pintype "passive"))
      (node (ref "J6") (pin "6") (pinfunction "6_6") (pintype "passive"))
    )
    (net (code "96") (name "Net-(IC1-ROM1-Pad38)") (class "Default")
      (node (ref "IC1-ROM1") (pin "38") (pinfunction "38_38") (pintype "passive"))
      (node (ref "J6") (pin "5") (pinfunction "5_5") (pintype "passive"))
    )
    (net (code "97") (name "Net-(IC1-ROM1-Pad39)") (class "Default")
      (node (ref "IC1-ROM1") (pin "39") (pinfunction "39_39") (pintype "passive"))
      (node (ref "J6") (pin "4") (pinfunction "4_4") (pintype "passive"))
    )
    (net (code "98") (name "Net-(IC1-ROM1-Pad40)") (class "Default")
      (node (ref "IC1-ROM1") (pin "40") (pinfunction "40_40") (pintype "passive"))
      (node (ref "J6") (pin "3") (pinfunction "3_3") (pintype "passive"))
    )
    (net (code "99") (name "Net-(IC1-ROM1-Pad41)") (class "Default")
      (node (ref "IC1-ROM1") (pin "41") (pinfunction "41_41") (pintype "passive"))
      (node (ref "J6") (pin "2") (pinfunction "2_2") (pintype "passive"))
    )
    (net (code "100") (name "Net-(IC1-ROM1-Pad42)") (class "Default")
      (node (ref "IC1-ROM1") (pin "42") (pinfunction "42_42") (pintype "passive"))
      (node (ref "J6") (pin "1") (pinfunction "1_1") (pintype "passive"))
    )
    (net (code "101") (name "Net-(IC2-ROM2-Pad1)") (class "Default")
      (node (ref "IC2-ROM2") (pin "1") (pinfunction "1_1") (pintype "passive"))
      (node (ref "J7") (pin "21") (pinfunction "21_21") (pintype "passive"))
    )
    (net (code "102") (name "Net-(IC2-ROM2-Pad2)") (class "Default")
      (node (ref "IC2-ROM2") (pin "2") (pinfunction "2_2") (pintype "passive"))
      (node (ref "J7") (pin "20") (pinfunction "20_20") (pintype "passive"))
    )
    (net (code "103") (name "Net-(IC2-ROM2-Pad3)") (class "Default")
      (node (ref "IC2-ROM2") (pin "3") (pinfunction "3_3") (pintype "passive"))
      (node (ref "J7") (pin "19") (pinfunction "19_19") (pintype "passive"))
    )
    (net (code "104") (name "Net-(IC2-ROM2-Pad4)") (class "Default")
      (node (ref "IC2-ROM2") (pin "4") (pinfunction "4_4") (pintype "passive"))
      (node (ref "J7") (pin "18") (pinfunction "18_18") (pintype "passive"))
    )
    (net (code "105") (name "Net-(IC2-ROM2-Pad5)") (class "Default")
      (node (ref "IC2-ROM2") (pin "5") (pinfunction "5_5") (pintype "passive"))
      (node (ref "J7") (pin "17") (pinfunction "17_17") (pintype "passive"))
    )
    (net (code "106") (name "Net-(IC2-ROM2-Pad6)") (class "Default")
      (node (ref "IC2-ROM2") (pin "6") (pinfunction "6_6") (pintype "passive"))
      (node (ref "J7") (pin "16") (pinfunction "16_16") (pintype "passive"))
    )
    (net (code "107") (name "Net-(IC2-ROM2-Pad7)") (class "Default")
      (node (ref "IC2-ROM2") (pin "7") (pinfunction "7_7") (pintype "passive"))
      (node (ref "J7") (pin "15") (pinfunction "15_15") (pintype "passive"))
    )
    (net (code "108") (name "Net-(IC2-ROM2-Pad11)") (class "Default")
      (node (ref "IC2-ROM2") (pin "11") (pinfunction "11_11") (pintype "passive"))
      (node (ref "J7") (pin "11") (pinfunction "11_11") (pintype "passive"))
    )
    (net (code "109") (name "Net-(IC2-ROM2-Pad13)") (class "Default")
      (node (ref "IC2-ROM2") (pin "13") (pinfunction "13_13") (pintype "passive"))
      (node (ref "J7") (pin "9") (pinfunction "9_9") (pintype "passive"))
    )
    (net (code "110") (name "Net-(IC2-ROM2-Pad32)") (class "Default")
      (node (ref "IC2-ROM2") (pin "32") (pinfunction "32_32") (pintype "passive"))
      (node (ref "J8") (pin "11") (pinfunction "11_11") (pintype "passive"))
    )
    (net (code "111") (name "Net-(IC2-ROM2-Pad33)") (class "Default")
      (node (ref "IC2-ROM2") (pin "33") (pinfunction "33_33") (pintype "passive"))
      (node (ref "J8") (pin "10") (pinfunction "10_10") (pintype "passive"))
    )
    (net (code "112") (name "Net-(IC2-ROM2-Pad34)") (class "Default")
      (node (ref "IC2-ROM2") (pin "34") (pinfunction "34_34") (pintype "passive"))
      (node (ref "J8") (pin "9") (pinfunction "9_9") (pintype "passive"))
    )
    (net (code "113") (name "Net-(IC2-ROM2-Pad35)") (class "Default")
      (node (ref "IC2-ROM2") (pin "35") (pinfunction "35_35") (pintype "passive"))
      (node (ref "J8") (pin "8") (pinfunction "8_8") (pintype "passive"))
    )
    (net (code "114") (name "Net-(IC2-ROM2-Pad36)") (class "Default")
      (node (ref "IC2-ROM2") (pin "36") (pinfunction "36_36") (pintype "passive"))
      (node (ref "J8") (pin "7") (pinfunction "7_7") (pintype "passive"))
    )
    (net (code "115") (name "Net-(IC2-ROM2-Pad37)") (class "Default")
      (node (ref "IC2-ROM2") (pin "37") (pinfunction "37_37") (pintype "passive"))
      (node (ref "J8") (pin "6") (pinfunction "6_6") (pintype "passive"))
    )
    (net (code "116") (name "Net-(IC2-ROM2-Pad38)") (class "Default")
      (node (ref "IC2-ROM2") (pin "38") (pinfunction "38_38") (pintype "passive"))
      (node (ref "J8") (pin "5") (pinfunction "5_5") (pintype "passive"))
    )
    (net (code "117") (name "Net-(IC2-ROM2-Pad39)") (class "Default")
      (node (ref "IC2-ROM2") (pin "39") (pinfunction "39_39") (pintype "passive"))
      (node (ref "J8") (pin "4") (pinfunction "4_4") (pintype "passive"))
    )
    (net (code "118") (name "Net-(IC2-ROM2-Pad40)") (class "Default")
      (node (ref "IC2-ROM2") (pin "40") (pinfunction "40_40") (pintype "passive"))
      (node (ref "J8") (pin "3") (pinfunction "3_3") (pintype "passive"))
    )
    (net (code "119") (name "Net-(IC2-ROM2-Pad41)") (class "Default")
      (node (ref "IC2-ROM2") (pin "41") (pinfunction "41_41") (pintype "passive"))
      (node (ref "J8") (pin "2") (pinfunction "2_2") (pintype "passive"))
    )
    (net (code "120") (name "Net-(IC2-ROM2-Pad42)") (class "Default")
      (node (ref "IC2-ROM2") (pin "42") (pinfunction "42_42") (pintype "passive"))
      (node (ref "J8") (pin "1") (pinfunction "1_1") (pintype "passive"))
    )
    (net (code "121") (name "VCC") (class "Default")
      (node (ref "C1") (pin "1") (pinfunction "1_1") (pintype "passive"))
      (node (ref "C2") (pin "2") (pinfunction "2_2") (pintype "passive"))
      (node (ref "C5") (pin "2") (pinfunction "2_2") (pintype "passive"))
      (node (ref "C6") (pin "1") (pinfunction "+_1") (pintype "passive"))
      (node (ref "IC1-ROM1") (pin "22") (pinfunction "22_22") (pintype "passive"))
      (node (ref "IC2-ROM2") (pin "22") (pinfunction "22_22") (pintype "passive"))
      (node (ref "IC3") (pin "20") (pinfunction "VCC_20") (pintype "passive"))
      (node (ref "IC4") (pin "20") (pinfunction "VCC_20") (pintype "passive"))
      (node (ref "IC5") (pin "14") (pinfunction "VCC_14") (pintype "passive"))
      (node (ref "J11") (pin "41") (pinfunction "41_41") (pintype "passive"))
      (node (ref "J11") (pin "42") (pinfunction "42_42") (pintype "passive"))
      (node (ref "J6") (pin "21") (pinfunction "21_21") (pintype "passive"))
      (node (ref "J8") (pin "21") (pinfunction "21_21") (pintype "passive"))
      (node (ref "R14") (pin "2") (pinfunction "2_2") (pintype "passive"))
      (node (ref "R15") (pin "2") (pinfunction "2_2") (pintype "passive"))
    )
    (net (code "122") (name "unconnected-(IC5-1A-Pad1)") (class "Default")
      (node (ref "IC5") (pin "1") (pinfunction "1A_1") (pintype "passive+no_connect"))
    )
    (net (code "123") (name "unconnected-(IC5-1Y-Pad2)") (class "Default")
      (node (ref "IC5") (pin "2") (pinfunction "1Y_2") (pintype "passive+no_connect"))
    )
    (net (code "124") (name "unconnected-(IC5-2A-Pad3)") (class "Default")
      (node (ref "IC5") (pin "3") (pinfunction "2A_3") (pintype "passive+no_connect"))
    )
    (net (code "125") (name "unconnected-(IC5-2Y-Pad4)") (class "Default")
      (node (ref "IC5") (pin "4") (pinfunction "2Y_4") (pintype "passive+no_connect"))
    )
    (net (code "126") (name "unconnected-(IC5-4A-Pad9)") (class "Default")
      (node (ref "IC5") (pin "9") (pinfunction "4A_9") (pintype "passive+no_connect"))
    )
    (net (code "127") (name "unconnected-(IC5-4Y-Pad8)") (class "Default")
      (node (ref "IC5") (pin "8") (pinfunction "4Y_8") (pintype "passive+no_connect"))
    )
    (net (code "128") (name "unconnected-(IC5-5A-Pad11)") (class "Default")
      (node (ref "IC5") (pin "11") (pinfunction "5A_11") (pintype "passive+no_connect"))
    )
    (net (code "129") (name "unconnected-(IC5-5Y-Pad10)") (class "Default")
      (node (ref "IC5") (pin "10") (pinfunction "5Y_10") (pintype "passive+no_connect"))
    )
    (net (code "130") (name "unconnected-(IC5-6A-Pad13)") (class "Default")
      (node (ref "IC5") (pin "13") (pinfunction "6A_13") (pintype "passive+no_connect"))
    )
    (net (code "131") (name "unconnected-(IC5-6Y-Pad12)") (class "Default")
      (node (ref "IC5") (pin "12") (pinfunction "6Y_12") (pintype "passive+no_connect"))
    )
    (net (code "132") (name "unconnected-(J11-Pad20)") (class "Default")
      (node (ref "J11") (pin "20") (pinfunction "20_20") (pintype "passive+no_connect"))
    )
    (net (code "133") (name "unconnected-(J11-Pad21)") (class "Default")
      (node (ref "J11") (pin "21") (pinfunction "21_21") (pintype "passive+no_connect"))
    )
    (net (code "134") (name "unconnected-(J11-Pad27)") (class "Default")
      (node (ref "J11") (pin "27") (pinfunction "27_27") (pintype "passive+no_connect"))
    )
    (net (code "135") (name "unconnected-(J11-Pad28)") (class "Default")
      (node (ref "J11") (pin "28") (pinfunction "28_28") (pintype "passive+no_connect"))
    )
    (net (code "136") (name "unconnected-(J11-Pad29)") (class "Default")
      (node (ref "J11") (pin "29") (pinfunction "29_29") (pintype "passive+no_connect"))
    )
    (net (code "137") (name "unconnected-(J11-Pad39)") (class "Default")
      (node (ref "J11") (pin "39") (pinfunction "39_39") (pintype "passive+no_connect"))
    )
  )
)
